# motor_breakout.net
KiCad netlist of a schematic drawn in EAGLE
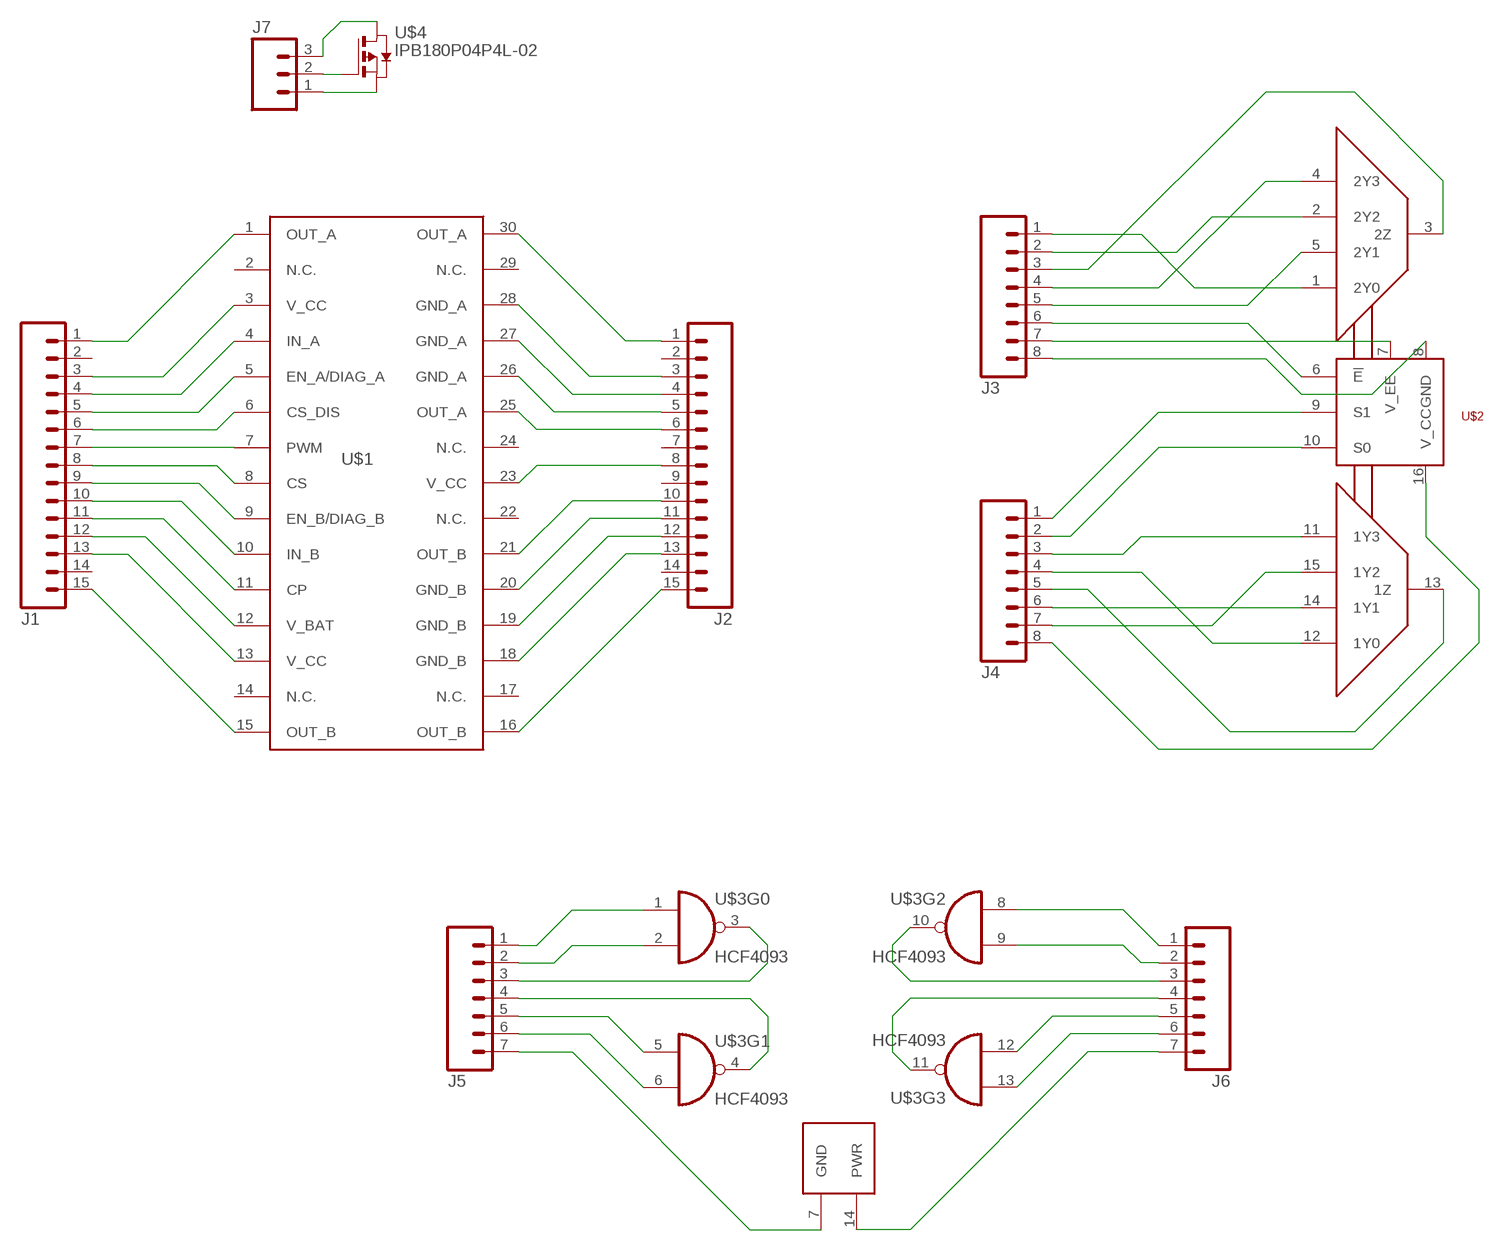
[diagram p0: schematic, sheet 1]

(export (version "E")
  (design (tool "Eeschema 10.0.6"))
  (components
    (comp (ref "J1")
      (value "M15")
      (footprint "eagle-import:1X15")
      (libsource (lib "eagle-import") (part "M15"))
    )
    (comp (ref "J2")
      (value "M15")
      (footprint "eagle-import:1X15")
      (libsource (lib "eagle-import") (part "M15"))
    )
    (comp (ref "J3")
      (value "M08SILK_FEMALE_PTH")
      (footprint "eagle-import:1X08")
      (libsource (lib "eagle-import") (part "M08SILK_FEMALE_PTH"))
    )
    (comp (ref "J4")
      (value "M08SILK_FEMALE_PTH")
      (footprint "eagle-import:1X08")
      (libsource (lib "eagle-import") (part "M08SILK_FEMALE_PTH"))
    )
    (comp (ref "J5")
      (value "M07")
      (footprint "eagle-import:1X07")
      (libsource (lib "eagle-import") (part "M07"))
    )
    (comp (ref "J6")
      (value "M07")
      (footprint "eagle-import:1X07")
      (libsource (lib "eagle-import") (part "M07"))
    )
    (comp (ref "J7")
      (value "M03PTH")
      (footprint "eagle-import:1X03")
      (libsource (lib "eagle-import") (part "M03PTH"))
    )
    (comp (ref "U$1")
      (value "VNH5019A-E")
      (footprint "eagle-import:MULTIPOWERSO-30")
      (libsource (lib "eagle-import") (part "VNH5019A-E"))
    )
    (comp (ref "U$2")
      (value "74HC4052-Q100")
      (footprint "eagle-import:SO16")
      (libsource (lib "eagle-import") (part "74HC4052-Q100"))
    )
    (comp (ref "U$3")
      (value "HCF4093")
      (footprint "eagle-import:SO14")
      (libsource (lib "eagle-import") (part "HCF4093"))
    )
    (comp (ref "U$4")
      (value "IPB180P04P4L-02")
      (footprint "eagle-import:PG-TO263-7-3")
      (libsource (lib "eagle-import") (part "IPB180P04P4L-02"))
    )
  )
  (nets
    (net (code "1") (name "/GND_A") (class "Default")
      (node (ref "J2") (pin "3") (pinfunction "3_3") (pintype "passive"))
      (node (ref "J2") (pin "4") (pinfunction "4_4") (pintype "passive"))
      (node (ref "J2") (pin "5") (pinfunction "5_5") (pintype "passive"))
      (node (ref "U$1") (pin "26") (pinfunction "GND_A_26") (pintype "bidirectional"))
      (node (ref "U$1") (pin "27") (pinfunction "GND_A_27") (pintype "bidirectional"))
      (node (ref "U$1") (pin "28") (pinfunction "GND_A_28") (pintype "bidirectional"))
    )
    (net (code "2") (name "/GND_B") (class "Default")
      (node (ref "J2") (pin "11") (pinfunction "11_11") (pintype "passive"))
      (node (ref "J2") (pin "12") (pinfunction "12_12") (pintype "passive"))
      (node (ref "J2") (pin "13") (pinfunction "13_13") (pintype "passive"))
      (node (ref "U$1") (pin "18") (pinfunction "GND_B_18") (pintype "bidirectional"))
      (node (ref "U$1") (pin "19") (pinfunction "GND_B_19") (pintype "bidirectional"))
      (node (ref "U$1") (pin "20") (pinfunction "GND_B_20") (pintype "bidirectional"))
    )
    (net (code "3") (name "/OUT_A") (class "Default")
      (node (ref "J1") (pin "1") (pinfunction "1_1") (pintype "passive"))
      (node (ref "J2") (pin "1") (pinfunction "1_1") (pintype "passive"))
      (node (ref "J2") (pin "6") (pinfunction "6_6") (pintype "passive"))
      (node (ref "U$1") (pin "1") (pinfunction "OUT_A_1") (pintype "bidirectional"))
      (node (ref "U$1") (pin "25") (pinfunction "OUT_A_25") (pintype "bidirectional"))
      (node (ref "U$1") (pin "30") (pinfunction "OUT_A_30") (pintype "bidirectional"))
    )
    (net (code "4") (name "/OUT_B") (class "Default")
      (node (ref "J1") (pin "15") (pinfunction "15_15") (pintype "passive"))
      (node (ref "J2") (pin "10") (pinfunction "10_10") (pintype "passive"))
      (node (ref "J2") (pin "15") (pinfunction "15_15") (pintype "passive"))
      (node (ref "U$1") (pin "15") (pinfunction "OUT_B_15") (pintype "bidirectional"))
      (node (ref "U$1") (pin "16") (pinfunction "OUT_B_16") (pintype "bidirectional"))
      (node (ref "U$1") (pin "21") (pinfunction "OUT_B_21") (pintype "bidirectional"))
    )
    (net (code "5") (name "/VCC") (class "Default")
      (node (ref "J1") (pin "13") (pinfunction "13_13") (pintype "passive"))
      (node (ref "J1") (pin "3") (pinfunction "3_3") (pintype "passive"))
      (node (ref "J2") (pin "8") (pinfunction "8_8") (pintype "passive"))
      (node (ref "U$1") (pin "13") (pinfunction "V_CC_13") (pintype "bidirectional"))
      (node (ref "U$1") (pin "23") (pinfunction "V_CC_23") (pintype "bidirectional"))
      (node (ref "U$1") (pin "3") (pinfunction "V_CC_3") (pintype "bidirectional"))
    )
    (net (code "6") (name "Net-(J7-Pad1)") (class "Default")
      (node (ref "J7") (pin "1") (pinfunction "1_1") (pintype "passive"))
      (node (ref "U$4") (pin "2") (pinfunction "S_2") (pintype "passive"))
      (node (ref "U$4") (pin "3") (pinfunction "S_3") (pintype "passive"))
      (node (ref "U$4") (pin "5") (pinfunction "S_5") (pintype "passive"))
      (node (ref "U$4") (pin "6") (pinfunction "S_6") (pintype "passive"))
      (node (ref "U$4") (pin "7") (pinfunction "S_7") (pintype "passive"))
    )
    (net (code "7") (name "Net-(U$1-CP)") (class "Default")
      (node (ref "J1") (pin "11") (pinfunction "11_11") (pintype "passive"))
      (node (ref "U$1") (pin "11") (pinfunction "CP_11") (pintype "bidirectional"))
    )
    (net (code "8") (name "Net-(U$1-CS)") (class "Default")
      (node (ref "J1") (pin "8") (pinfunction "8_8") (pintype "passive"))
      (node (ref "U$1") (pin "8") (pinfunction "CS_8") (pintype "bidirectional"))
    )
    (net (code "9") (name "Net-(U$1-CS_DIS)") (class "Default")
      (node (ref "J1") (pin "6") (pinfunction "6_6") (pintype "passive"))
      (node (ref "U$1") (pin "6") (pinfunction "CS_DIS_6") (pintype "bidirectional"))
    )
    (net (code "10") (name "Net-(U$1-EN_A{slash}DIAG_A)") (class "Default")
      (node (ref "J1") (pin "5") (pinfunction "5_5") (pintype "passive"))
      (node (ref "U$1") (pin "5") (pinfunction "EN_A/DIAG_A_5") (pintype "bidirectional"))
    )
    (net (code "11") (name "Net-(U$1-EN_B{slash}DIAG_B)") (class "Default")
      (node (ref "J1") (pin "9") (pinfunction "9_9") (pintype "passive"))
      (node (ref "U$1") (pin "9") (pinfunction "EN_B/DIAG_B_9") (pintype "bidirectional"))
    )
    (net (code "12") (name "Net-(U$1-IN_A)") (class "Default")
      (node (ref "J1") (pin "4") (pinfunction "4_4") (pintype "passive"))
      (node (ref "U$1") (pin "4") (pinfunction "IN_A_4") (pintype "bidirectional"))
    )
    (net (code "13") (name "Net-(U$1-IN_B)") (class "Default")
      (node (ref "J1") (pin "10") (pinfunction "10_10") (pintype "passive"))
      (node (ref "U$1") (pin "10") (pinfunction "IN_B_10") (pintype "bidirectional"))
    )
    (net (code "14") (name "Net-(U$1-PWM)") (class "Default")
      (node (ref "J1") (pin "7") (pinfunction "7_7") (pintype "passive"))
      (node (ref "U$1") (pin "7") (pinfunction "PWM_7") (pintype "bidirectional"))
    )
    (net (code "15") (name "Net-(U$1-V_BAT)") (class "Default")
      (node (ref "J1") (pin "12") (pinfunction "12_12") (pintype "passive"))
      (node (ref "U$1") (pin "12") (pinfunction "V_BAT_12") (pintype "bidirectional"))
    )
    (net (code "16") (name "Net-(U$2-1Y0)") (class "Default")
      (node (ref "J4") (pin "4") (pinfunction "4_4") (pintype "passive"))
      (node (ref "U$2") (pin "12") (pinfunction "1Y0_12") (pintype "bidirectional"))
    )
    (net (code "17") (name "Net-(U$2-1Y1)") (class "Default")
      (node (ref "J4") (pin "6") (pinfunction "6_6") (pintype "passive"))
      (node (ref "U$2") (pin "14") (pinfunction "1Y1_14") (pintype "bidirectional"))
    )
    (net (code "18") (name "Net-(U$2-1Y2)") (class "Default")
      (node (ref "J4") (pin "7") (pinfunction "7_7") (pintype "passive"))
      (node (ref "U$2") (pin "15") (pinfunction "1Y2_15") (pintype "bidirectional"))
    )
    (net (code "19") (name "Net-(U$2-1Y3)") (class "Default")
      (node (ref "J4") (pin "3") (pinfunction "3_3") (pintype "passive"))
      (node (ref "U$2") (pin "11") (pinfunction "1Y3_11") (pintype "bidirectional"))
    )
    (net (code "20") (name "Net-(U$2-1Z)") (class "Default")
      (node (ref "J4") (pin "5") (pinfunction "5_5") (pintype "passive"))
      (node (ref "U$2") (pin "13") (pinfunction "1Z_13") (pintype "bidirectional"))
    )
    (net (code "21") (name "Net-(U$2-2Y0)") (class "Default")
      (node (ref "J3") (pin "1") (pinfunction "1_1") (pintype "passive"))
      (node (ref "U$2") (pin "1") (pinfunction "2Y0_1") (pintype "bidirectional"))
    )
    (net (code "22") (name "Net-(U$2-2Y1)") (class "Default")
      (node (ref "J3") (pin "5") (pinfunction "5_5") (pintype "passive"))
      (node (ref "U$2") (pin "5") (pinfunction "2Y1_5") (pintype "bidirectional"))
    )
    (net (code "23") (name "Net-(U$2-2Y2)") (class "Default")
      (node (ref "J3") (pin "2") (pinfunction "2_2") (pintype "passive"))
      (node (ref "U$2") (pin "2") (pinfunction "2Y2_2") (pintype "bidirectional"))
    )
    (net (code "24") (name "Net-(U$2-2Y3)") (class "Default")
      (node (ref "J3") (pin "4") (pinfunction "4_4") (pintype "passive"))
      (node (ref "U$2") (pin "4") (pinfunction "2Y3_4") (pintype "bidirectional"))
    )
    (net (code "25") (name "Net-(U$2-2Z)") (class "Default")
      (node (ref "J3") (pin "3") (pinfunction "3_3") (pintype "passive"))
      (node (ref "U$2") (pin "3") (pinfunction "2Z_3") (pintype "bidirectional"))
    )
    (net (code "26") (name "Net-(U$2-GND)") (class "Default")
      (node (ref "J3") (pin "8") (pinfunction "8_8") (pintype "passive"))
      (node (ref "U$2") (pin "8") (pinfunction "GND_8") (pintype "bidirectional"))
    )
    (net (code "27") (name "Net-(U$2-S0)") (class "Default")
      (node (ref "J4") (pin "2") (pinfunction "2_2") (pintype "passive"))
      (node (ref "U$2") (pin "10") (pinfunction "S0_10") (pintype "bidirectional"))
    )
    (net (code "28") (name "Net-(U$2-S1)") (class "Default")
      (node (ref "J4") (pin "1") (pinfunction "1_1") (pintype "passive"))
      (node (ref "U$2") (pin "9") (pinfunction "S1_9") (pintype "bidirectional"))
    )
    (net (code "29") (name "Net-(U$2-V_CC)") (class "Default")
      (node (ref "J4") (pin "8") (pinfunction "8_8") (pintype "passive"))
      (node (ref "U$2") (pin "16") (pinfunction "V_CC_16") (pintype "bidirectional"))
    )
    (net (code "30") (name "Net-(U$2-V_EE)") (class "Default")
      (node (ref "J3") (pin "7") (pinfunction "7_7") (pintype "passive"))
      (node (ref "U$2") (pin "7") (pinfunction "V_EE_7") (pintype "bidirectional"))
    )
    (net (code "31") (name "Net-(U$2-~{E})") (class "Default")
      (node (ref "J3") (pin "6") (pinfunction "6_6") (pintype "passive"))
      (node (ref "U$2") (pin "6") (pinfunction "~{E}_6") (pintype "bidirectional"))
    )
    (net (code "32") (name "Net-(U$3A-GND)") (class "Default")
      (node (ref "J5") (pin "7") (pinfunction "7_7") (pintype "passive"))
      (node (ref "U$3") (pin "7") (pinfunction "GND_7") (pintype "bidirectional"))
    )
    (net (code "33") (name "Net-(U$3A-PWR)") (class "Default")
      (node (ref "J6") (pin "7") (pinfunction "7_7") (pintype "passive"))
      (node (ref "U$3") (pin "14") (pinfunction "PWR_14") (pintype "bidirectional"))
    )
    (net (code "34") (name "Net-(U$3B-I0)") (class "Default")
      (node (ref "J5") (pin "1") (pinfunction "1_1") (pintype "passive"))
      (node (ref "U$3") (pin "1") (pinfunction "I0_1") (pintype "input"))
    )
    (net (code "35") (name "Net-(U$3B-I1)") (class "Default")
      (node (ref "J5") (pin "2") (pinfunction "2_2") (pintype "passive"))
      (node (ref "U$3") (pin "2") (pinfunction "I1_2") (pintype "input"))
    )
    (net (code "36") (name "Net-(U$3B-O)") (class "Default")
      (node (ref "J5") (pin "3") (pinfunction "3_3") (pintype "passive"))
      (node (ref "U$3") (pin "3") (pinfunction "O_3") (pintype "output"))
    )
    (net (code "37") (name "Net-(U$3C-I0)") (class "Default")
      (node (ref "J5") (pin "5") (pinfunction "5_5") (pintype "passive"))
      (node (ref "U$3") (pin "5") (pinfunction "I0_5") (pintype "input"))
    )
    (net (code "38") (name "Net-(U$3C-I1)") (class "Default")
      (node (ref "J5") (pin "6") (pinfunction "6_6") (pintype "passive"))
      (node (ref "U$3") (pin "6") (pinfunction "I1_6") (pintype "input"))
    )
    (net (code "39") (name "Net-(U$3C-O)") (class "Default")
      (node (ref "J5") (pin "4") (pinfunction "4_4") (pintype "passive"))
      (node (ref "U$3") (pin "4") (pinfunction "O_4") (pintype "output"))
    )
    (net (code "40") (name "Net-(U$3D-I0)") (class "Default")
      (node (ref "J6") (pin "1") (pinfunction "1_1") (pintype "passive"))
      (node (ref "U$3") (pin "8") (pinfunction "I0_8") (pintype "input"))
    )
    (net (code "41") (name "Net-(U$3D-I1)") (class "Default")
      (node (ref "J6") (pin "2") (pinfunction "2_2") (pintype "passive"))
      (node (ref "U$3") (pin "9") (pinfunction "I1_9") (pintype "input"))
    )
    (net (code "42") (name "Net-(U$3D-O)") (class "Default")
      (node (ref "J6") (pin "3") (pinfunction "3_3") (pintype "passive"))
      (node (ref "U$3") (pin "10") (pinfunction "O_10") (pintype "output"))
    )
    (net (code "43") (name "Net-(U$3E-I0)") (class "Default")
      (node (ref "J6") (pin "6") (pinfunction "6_6") (pintype "passive"))
      (node (ref "U$3") (pin "13") (pinfunction "I0_13") (pintype "input"))
    )
    (net (code "44") (name "Net-(U$3E-I1)") (class "Default")
      (node (ref "J6") (pin "5") (pinfunction "5_5") (pintype "passive"))
      (node (ref "U$3") (pin "12") (pinfunction "I1_12") (pintype "input"))
    )
    (net (code "45") (name "Net-(U$3E-O)") (class "Default")
      (node (ref "J6") (pin "4") (pinfunction "4_4") (pintype "passive"))
      (node (ref "U$3") (pin "11") (pinfunction "O_11") (pintype "output"))
    )
    (net (code "46") (name "Net-(U$4-D)") (class "Default")
      (node (ref "J7") (pin "3") (pinfunction "3_3") (pintype "passive"))
      (node (ref "U$4") (pin "8") (pinfunction "D_8") (pintype "passive"))
    )
    (net (code "47") (name "Net-(U$4-G)") (class "Default")
      (node (ref "J7") (pin "2") (pinfunction "2_2") (pintype "passive"))
      (node (ref "U$4") (pin "1") (pinfunction "G_1") (pintype "passive"))
    )
    (net (code "48") (name "unconnected-(J1-Pad2)") (class "Default")
      (node (ref "J1") (pin "2") (pinfunction "2_2") (pintype "passive"))
    )
    (net (code "49") (name "unconnected-(J1-Pad14)") (class "Default")
      (node (ref "J1") (pin "14") (pinfunction "14_14") (pintype "passive"))
    )
    (net (code "50") (name "unconnected-(J2-Pad2)") (class "Default")
      (node (ref "J2") (pin "2") (pinfunction "2_2") (pintype "passive"))
    )
    (net (code "51") (name "unconnected-(J2-Pad7)") (class "Default")
      (node (ref "J2") (pin "7") (pinfunction "7_7") (pintype "passive"))
    )
    (net (code "52") (name "unconnected-(J2-Pad9)") (class "Default")
      (node (ref "J2") (pin "9") (pinfunction "9_9") (pintype "passive"))
    )
    (net (code "53") (name "unconnected-(J2-Pad14)") (class "Default")
      (node (ref "J2") (pin "14") (pinfunction "14_14") (pintype "passive"))
    )
    (net (code "54") (name "unconnected-(U$1-N.C.-Pad2)") (class "Default")
      (node (ref "U$1") (pin "2") (pinfunction "N.C._2") (pintype "bidirectional"))
    )
    (net (code "55") (name "unconnected-(U$1-N.C.-Pad14)") (class "Default")
      (node (ref "U$1") (pin "14") (pinfunction "N.C._14") (pintype "bidirectional"))
    )
    (net (code "56") (name "unconnected-(U$1-N.C.-Pad17)") (class "Default")
      (node (ref "U$1") (pin "17") (pinfunction "N.C._17") (pintype "bidirectional"))
    )
    (net (code "57") (name "unconnected-(U$1-N.C.-Pad22)") (class "Default")
      (node (ref "U$1") (pin "22") (pinfunction "N.C._22") (pintype "bidirectional"))
    )
    (net (code "58") (name "unconnected-(U$1-N.C.-Pad24)") (class "Default")
      (node (ref "U$1") (pin "24") (pinfunction "N.C._24") (pintype "bidirectional"))
    )
    (net (code "59") (name "unconnected-(U$1-N.C.-Pad29)") (class "Default")
      (node (ref "U$1") (pin "29") (pinfunction "N.C._29") (pintype "bidirectional"))
    )
  )
)
